# Dongle.net
KiCad netlist of a schematic drawn in Altium Designer
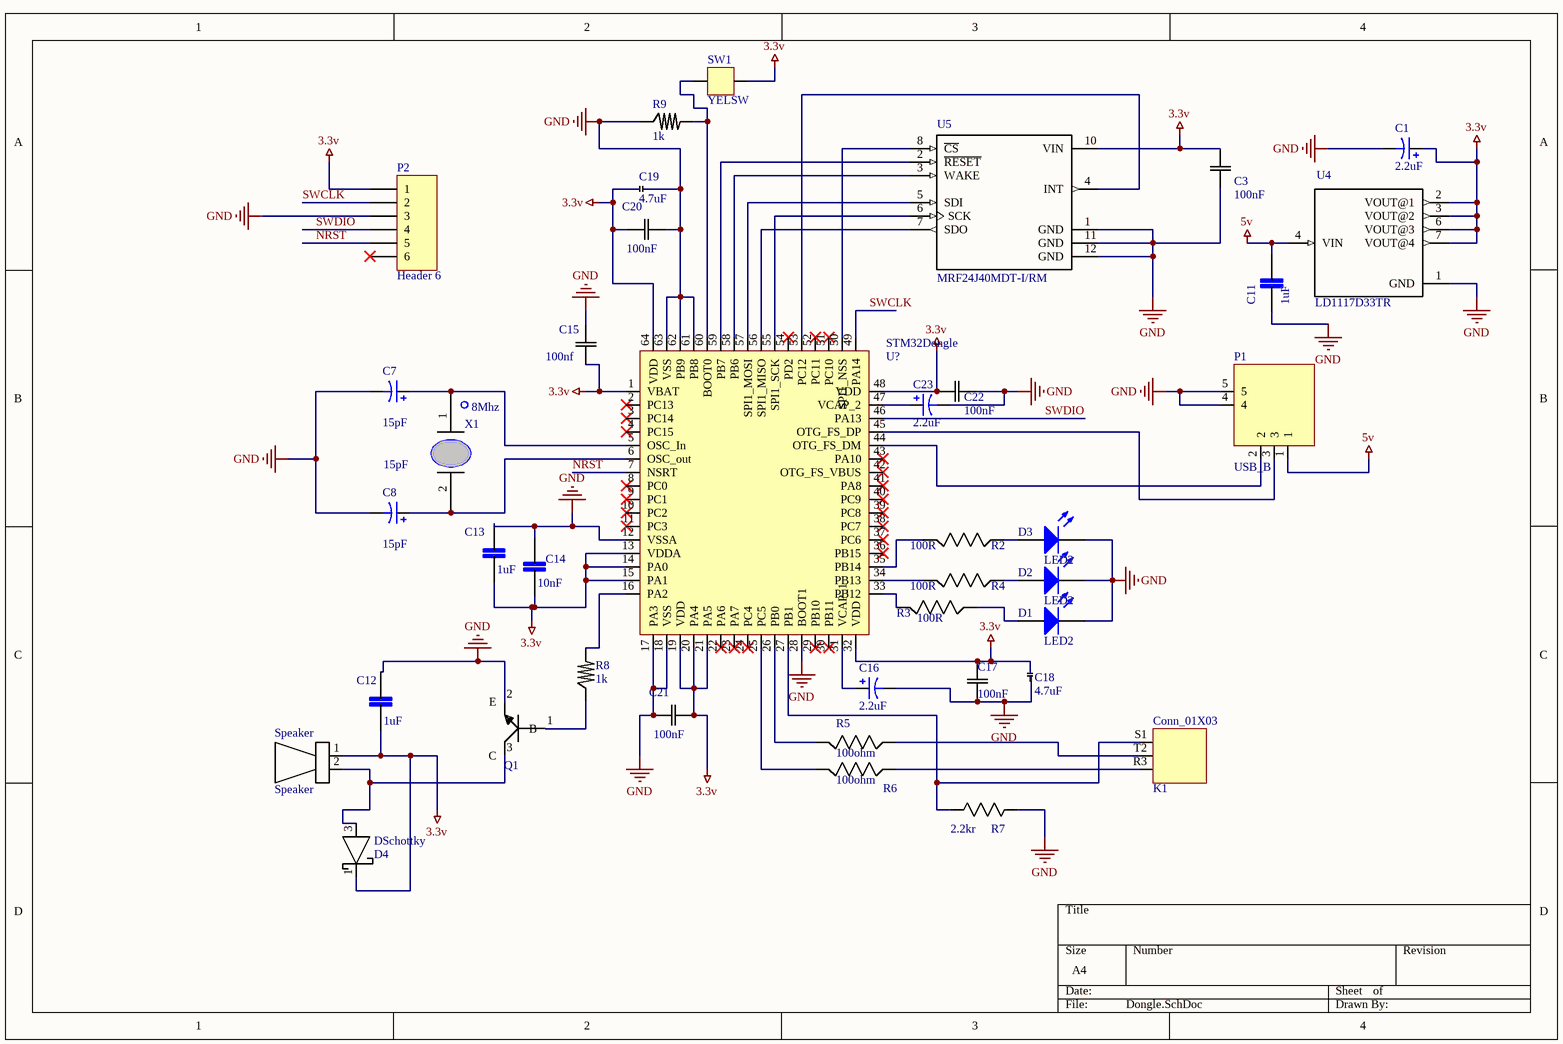
[diagram p0: Dongle.SchDoc]

(export (version "E")
  (design (tool "Eeschema 10.0.6"))
  (components
    (comp (ref "8Mhz")
      (value "X1")
      (footprint "XTAL_ABLS2-24.000MHZ-D4YF-T")
      (libsource (lib "8MhzCrystal") (part "8Mhz"))
    )
    (comp (ref "C1")
      (value "2.2uF")
      (footprint "C0805")
      (description "Polarized Capacitor (Surface Mount)")
      (fields (field (name "Comment") "Cap Pol3") (field (name "PUBLISHER") "Altium Limited"))
      (libsource (lib "Miscellaneous Devices") (part "Cap Pol3"))
    )
    (comp (ref "C3")
      (value "100nF")
      (footprint "CAPC2013X110N")
      (description "Capacitor; Ceramic; Cap; .100UF ; Tol+-10%; SMD; Vol-Rtg 50V; X7R, Tape/Reel")
      (fields (field (name "MP") "C0805C104K5RACTU") (field (name "MF") "Kemet"))
      (libsource (lib "100nF-C0805C104K5RACTU") (part "C0805C104K5RACTU"))
    )
    (comp (ref "C7")
      (value "15pF")
      (footprint "C0805")
      (description "Polarized Capacitor (Surface Mount)")
      (fields (field (name "ALTIUM_VALUE") "15pF") (field (name "PUBLISHER") "Altium Limited"))
      (libsource (lib "Miscellaneous Devices") (part "Cap Pol3"))
    )
    (comp (ref "C8")
      (value "15pF")
      (footprint "C0805")
      (description "Polarized Capacitor (Surface Mount)")
      (fields (field (name "Comment") "Cap Pol3") (field (name "PUBLISHER") "Altium Limited"))
      (libsource (lib "Miscellaneous Devices") (part "Cap Pol3"))
    )
    (comp (ref "C11")
      (value "1uF")
      (footprint "INDC2012X87N")
      (description "CAP CER 1UF 25V X5R 0805")
      (fields (field (name "MF") "TDK") (field (name "MP") "C2012X5R1E105M085AC"))
      (libsource (lib "1uF") (part "C2012X5R1E105M085AC"))
    )
    (comp (ref "C12")
      (value "1uF")
      (footprint "INDC2012X87N")
      (description "CAP CER 1UF 25V X5R 0805")
      (fields (field (name "MF") "TDK") (field (name "MP") "C2012X5R1E105M085AC"))
      (libsource (lib "1uF") (part "C2012X5R1E105M085AC"))
    )
    (comp (ref "C13")
      (value "1uF")
      (footprint "INDC2012X87N")
      (description "CAP CER 1UF 25V X5R 0805")
      (fields (field (name "MF") "TDK") (field (name "MP") "C2012X5R1E105M085AC"))
      (libsource (lib "") (part "C2012X5R1E105M085AC_1"))
    )
    (comp (ref "C14")
      (value "10nF")
      (footprint "CAPC2012X135N")
      (description "CAP CER 10000PF 50V X7R 0805")
      (fields (field (name "MF") "Murata") (field (name "DIGI-KEY_PART_NUMBER") "490-1664-1-ND"))
      (libsource (lib "10nF") (part "GRM216R71H103KA01D"))
    )
    (comp (ref "C15")
      (value "100nf")
      (footprint "CAPC2013X110N")
      (description "Capacitor; Ceramic; Cap; .100UF ; Tol+-10%; SMD; Vol-Rtg 50V; X7R, Tape/Reel")
      (fields (field (name "MP") "C0805C104K5RACTU") (field (name "MF") "Kemet"))
      (libsource (lib "") (part "C0805C104K5RACTU_1"))
    )
    (comp (ref "C16")
      (value "2.2uF")
      (footprint "C0805")
      (description "Polarized Capacitor (Surface Mount)")
      (fields (field (name "Comment") "Cap Pol3") (field (name "PUBLISHER") "Altium Limited"))
      (libsource (lib "Miscellaneous Devices") (part "Cap Pol3"))
    )
    (comp (ref "C17")
      (value "100nF")
      (footprint "CAPC2013X110N")
      (description "Capacitor; Ceramic; Cap; .100UF ; Tol+-10%; SMD; Vol-Rtg 50V; X7R, Tape/Reel")
      (fields (field (name "MP") "C0805C104K5RACTU") (field (name "MF") "Kemet"))
      (libsource (lib "") (part "C0805C104K5RACTU_2"))
    )
    (comp (ref "C18") (value "4.7uF") (footprint "0805") (libsource (lib "4.7uF") (part "4.7uF")))
    (comp (ref "C19") (value "4.7uF") (footprint "0805") (libsource (lib "4.7uF") (part "4.7uF")))
    (comp (ref "C20")
      (value "100nF")
      (footprint "CAPC2013X110N")
      (description "Capacitor; Ceramic; Cap; .100UF ; Tol+-10%; SMD; Vol-Rtg 50V; X7R, Tape/Reel")
      (fields (field (name "MP") "C0805C104K5RACTU") (field (name "MF") "Kemet"))
      (libsource (lib "100nF-C0805C104K5RACTU") (part "C0805C104K5RACTU"))
    )
    (comp (ref "C21")
      (value "100nF")
      (footprint "CAPC2013X110N")
      (description "Capacitor; Ceramic; Cap; .100UF ; Tol+-10%; SMD; Vol-Rtg 50V; X7R, Tape/Reel")
      (fields (field (name "MP") "C0805C104K5RACTU") (field (name "MF") "Kemet"))
      (libsource (lib "100nF-C0805C104K5RACTU") (part "C0805C104K5RACTU"))
    )
    (comp (ref "C22")
      (value "100nF")
      (footprint "CAPC2013X110N")
      (description "Capacitor; Ceramic; Cap; .100UF ; Tol+-10%; SMD; Vol-Rtg 50V; X7R, Tape/Reel")
      (fields (field (name "MP") "C0805C104K5RACTU") (field (name "MF") "Kemet"))
      (libsource (lib "100nF-C0805C104K5RACTU") (part "C0805C104K5RACTU"))
    )
    (comp (ref "C23")
      (value "2.2uF")
      (footprint "C0805")
      (description "Polarized Capacitor (Surface Mount)")
      (fields (field (name "Comment") "Cap Pol3") (field (name "PUBLISHER") "Altium Limited"))
      (libsource (lib "Miscellaneous Devices") (part "Cap Pol3"))
    )
    (comp (ref "Conn_01X03")
      (value "K1")
      (footprint "PCBComponent_1")
      (libsource (lib "MiCInput") (part "Conn_01X03"))
    )
    (comp (ref "D1")
      (value "LED2")
      (footprint "3.2X1.6X1.1")
      (description "Typical RED, GREEN, YELLOW, AMBER GaAs LED")
      (fields (field (name "PUBLISHER") "Altium Limited"))
      (libsource (lib "Miscellaneous Devices") (part "LED2"))
    )
    (comp (ref "D2")
      (value "LED2")
      (footprint "3.2X1.6X1.1")
      (description "Typical RED, GREEN, YELLOW, AMBER GaAs LED")
      (fields (field (name "PUBLISHER") "Altium Limited"))
      (libsource (lib "Miscellaneous Devices") (part "LED2"))
    )
    (comp (ref "D3")
      (value "LED2")
      (footprint "3.2X1.6X1.1")
      (description "Typical RED, GREEN, YELLOW, AMBER GaAs LED")
      (fields (field (name "PUBLISHER") "Altium Limited"))
      (libsource (lib "Miscellaneous Devices") (part "LED2"))
    )
    (comp (ref "DSchottky")
      (value "D4")
      (footprint "SOT65P210X110-3N")
      (libsource (lib "DSchotkky") (part "DSchottky"))
    )
    (comp (ref "P1")
      (value "USB_B")
      (footprint "PCBComponent_1")
      (libsource (lib "USB_B_Female") (part "Component_1"))
    )
    (comp (ref "P2")
      (value "Header 6")
      (footprint "HDR1X6")
      (description "Header, 6-Pin")
      (fields (field (name "PUBLISHER") "Altium Limited"))
      (libsource (lib "Miscellaneous Connectors") (part "Header 6"))
    )
    (comp (ref "Q1")
      (value "BC846A-7-F")
      (footprint "SOT23-3")
      (description "TRANS NPN 65V 0.1A SOT23-3")
      (fields (field (name "MF") "Diodes Inc.") (field (name "DIGI-KEY_PART_NUMBER") "BC846A-7FDICT-ND"))
      (libsource (lib "NPN") (part "BC846A-7-F"))
    )
    (comp (ref "R2")
      (value "100R")
      (footprint "RESC2012X60")
      (description "RES SMD 100 OHM 1% 1/8W 0805")
      (fields (field (name "MP") "RC0805FR-07100RL") (field (name "MF") "Yageo"))
      (libsource (lib "RC0805FR-07100RL") (part "RC0805FR-07100RL"))
    )
    (comp (ref "R3")
      (value "100R")
      (footprint "RESC2012X60")
      (description "RES SMD 100 OHM 1% 1/8W 0805")
      (fields (field (name "MP") "RC0805FR-07100RL") (field (name "MF") "Yageo"))
      (libsource (lib "RC0805FR-07100RL") (part "RC0805FR-07100RL"))
    )
    (comp (ref "R4")
      (value "100R")
      (footprint "RESC2012X60")
      (description "RES SMD 100 OHM 1% 1/8W 0805")
      (fields (field (name "MP") "RC0805FR-07100RL") (field (name "MF") "Yageo"))
      (libsource (lib "RC0805FR-07100RL") (part "RC0805FR-07100RL"))
    )
    (comp (ref "R5")
      (value "100ohm")
      (footprint "RESC2012X60")
      (description "RES SMD 100 OHM 1% 1/8W 0805")
      (fields (field (name "MP") "RC0805FR-07100RL") (field (name "MF") "Yageo"))
      (libsource (lib "RC0805FR-07100RL") (part "RC0805FR-07100RL"))
    )
    (comp (ref "R6")
      (value "100ohm")
      (footprint "RESC2012X60")
      (description "RES SMD 100 OHM 1% 1/8W 0805")
      (fields (field (name "MP") "RC0805FR-07100RL") (field (name "MF") "Yageo"))
      (libsource (lib "RC0805FR-07100RL") (part "RC0805FR-07100RL"))
    )
    (comp (ref "R7")
      (value "2.2kr")
      (footprint "RESC2013X65N")
      (description "RES SMD 2.2K OHM 1% 1/8W 0805")
      (fields (field (name "MP") "RC0805FR-072K2L") (field (name "MF") "Yageo"))
      (libsource (lib "RC0805FR-072K2L") (part "RC0805FR-072K2L"))
    )
    (comp (ref "R8")
      (value "1k")
      (footprint "CAPC2012X140N")
      (description "1276-5272-1-ND")
      (libsource (lib "1k") (part "1kohm"))
    )
    (comp (ref "R9")
      (value "1k")
      (footprint "CAPC2012X140N")
      (description "1276-5272-1-ND")
      (libsource (lib "1k") (part "1kohm"))
    )
    (comp (ref "Speaker")
      (value "Speaker")
      (footprint "Speaker")
      (libsource (lib "Speaker") (part "Component_1"))
    )
    (comp (ref "STM32Dongle")
      (value "U?")
      (footprint "QFP50P1200X1200X160-64N")
      (description "497-11907-ND")
      (libsource (lib "STM32F415RGT6") (part "STM32Dongle"))
    )
    (comp (ref "SW1")
      (value "YELSW")
      (footprint "PCBComponent_1")
      (libsource (lib "EG2555-ND") (part "YELSW"))
    )
    (comp (ref "U4")
      (value "LD1117D33TR")
      (footprint "SOIC127P600X175-8N")
      (description "IC REG LINEAR 3.3V 800MA 8SO")
      (fields (field (name "MF") "STMicroelectronics"))
      (libsource (lib "LD1117D33TR") (part "LD1117D33TR"))
    )
    (comp (ref "U5")
      (value "MRF24J40MDT-I/RM")
      (footprint "XCVR_MRF24J40MDT-I/RM")
      (description "2.4 GHz IEEE 802.15.4 Certified Transceiver Module (+20 dBm), 12 MODULE Varies T/R")
      (fields (field (name "MF") "Microchip"))
      (libsource (lib "MRF24J40MDT-I_RM") (part "MRF24J40MDT-I/RM"))
    )
  )
  (nets
    (net (code "1") (name "/NRST") (class "Default")
      (node (ref "P2") (pin "5") (pinfunction "5_5") (pintype "passive"))
      (node (ref "STM32Dongle") (pin "7") (pinfunction "NSRT_7") (pintype "passive"))
    )
    (net (code "2") (name "/SWCLK") (class "Default")
      (node (ref "P2") (pin "2") (pinfunction "2_2") (pintype "passive"))
      (node (ref "STM32Dongle") (pin "49") (pinfunction "PA14_49") (pintype "passive"))
    )
    (net (code "3") (name "/SWDIO") (class "Default")
      (node (ref "P2") (pin "4") (pinfunction "4_4") (pintype "passive"))
      (node (ref "STM32Dongle") (pin "46") (pinfunction "PA13_46") (pintype "passive"))
    )
    (net (code "4") (name "3.3v") (class "Default")
      (node (ref "C1") (pin "1") (pinfunction "1_1") (pintype "passive"))
      (node (ref "C12") (pin "1") (pinfunction "1_1") (pintype "passive"))
      (node (ref "C13") (pin "1") (pinfunction "1_1") (pintype "passive"))
      (node (ref "C14") (pin "1") (pinfunction "1_1") (pintype "passive"))
      (node (ref "C15") (pin "1") (pinfunction "C1_1") (pintype "passive"))
      (node (ref "C17") (pin "1") (pinfunction "C1_1") (pintype "passive"))
      (node (ref "C18") (pin "P1") (pinfunction "P1_P1") (pintype "passive"))
      (node (ref "C19") (pin "P1") (pinfunction "P1_P1") (pintype "passive"))
      (node (ref "C20") (pin "1") (pinfunction "C1_1") (pintype "passive"))
      (node (ref "C21") (pin "2") (pinfunction "C2_2") (pintype "passive"))
      (node (ref "C22") (pin "1") (pinfunction "C1_1") (pintype "passive"))
      (node (ref "C3") (pin "1") (pinfunction "C1_1") (pintype "passive"))
      (node (ref "DSchottky") (pin "1") (pinfunction "1_1") (pintype "passive"))
      (node (ref "P2") (pin "1") (pinfunction "1_1") (pintype "passive"))
      (node (ref "STM32Dongle") (pin "1") (pinfunction "VBAT_1") (pintype "passive"))
      (node (ref "STM32Dongle") (pin "13") (pinfunction "VDDA_13") (pintype "passive"))
      (node (ref "STM32Dongle") (pin "14") (pinfunction "PA0_14") (pintype "passive"))
      (node (ref "STM32Dongle") (pin "15") (pinfunction "PA1_15") (pintype "passive"))
      (node (ref "STM32Dongle") (pin "19") (pinfunction "VDD_19") (pintype "passive"))
      (node (ref "STM32Dongle") (pin "20") (pinfunction "PA4_20") (pintype "passive"))
      (node (ref "STM32Dongle") (pin "21") (pinfunction "PA5_21") (pintype "passive"))
      (node (ref "STM32Dongle") (pin "32") (pinfunction "VDD_32") (pintype "passive"))
      (node (ref "STM32Dongle") (pin "48") (pinfunction "VDD_48") (pintype "passive"))
      (node (ref "STM32Dongle") (pin "64") (pinfunction "VDD_64") (pintype "passive"))
      (node (ref "SW1") (pin "3") (pinfunction "3_3") (pintype "passive"))
      (node (ref "Speaker") (pin "1") (pinfunction "1_1") (pintype "passive"))
      (node (ref "U4") (pin "2") (pinfunction "VOUT@1_2") (pintype "output"))
      (node (ref "U4") (pin "3") (pinfunction "VOUT@2_3") (pintype "output"))
      (node (ref "U4") (pin "6") (pinfunction "VOUT@3_6") (pintype "output"))
      (node (ref "U4") (pin "7") (pinfunction "VOUT@4_7") (pintype "output"))
      (node (ref "U5") (pin "10") (pinfunction "VIN_10") (pintype "power_in"))
    )
    (net (code "5") (name "5v") (class "Default")
      (node (ref "C11") (pin "2") (pinfunction "2_2") (pintype "passive"))
      (node (ref "P1") (pin "1") (pinfunction "1_1") (pintype "passive"))
      (node (ref "U4") (pin "4") (pinfunction "VIN_4") (pintype "input"))
    )
    (net (code "6") (name "GND") (class "Default")
      (node (ref "C1") (pin "2") (pinfunction "2_2") (pintype "passive"))
      (node (ref "C11") (pin "1") (pinfunction "1_1") (pintype "passive"))
      (node (ref "C12") (pin "2") (pinfunction "2_2") (pintype "passive"))
      (node (ref "C13") (pin "2") (pinfunction "2_2") (pintype "passive"))
      (node (ref "C14") (pin "2") (pinfunction "2_2") (pintype "passive"))
      (node (ref "C15") (pin "2") (pinfunction "C2_2") (pintype "passive"))
      (node (ref "C16") (pin "2") (pinfunction "2_2") (pintype "passive"))
      (node (ref "C17") (pin "2") (pinfunction "C2_2") (pintype "passive"))
      (node (ref "C18") (pin "P2") (pinfunction "P2_P2") (pintype "passive"))
      (node (ref "C19") (pin "P2") (pinfunction "P2_P2") (pintype "passive"))
      (node (ref "C20") (pin "2") (pinfunction "C2_2") (pintype "passive"))
      (node (ref "C21") (pin "1") (pinfunction "C1_1") (pintype "passive"))
      (node (ref "C22") (pin "2") (pinfunction "C2_2") (pintype "passive"))
      (node (ref "C23") (pin "2") (pinfunction "2_2") (pintype "passive"))
      (node (ref "C3") (pin "2") (pinfunction "C2_2") (pintype "passive"))
      (node (ref "C7") (pin "2") (pinfunction "2_2") (pintype "passive"))
      (node (ref "C8") (pin "2") (pinfunction "2_2") (pintype "passive"))
      (node (ref "D1") (pin "2") (pinfunction "K_2") (pintype "passive"))
      (node (ref "D2") (pin "2") (pinfunction "K_2") (pintype "passive"))
      (node (ref "D3") (pin "2") (pinfunction "K_2") (pintype "passive"))
      (node (ref "P1") (pin "4") (pinfunction "4_4") (pintype "passive"))
      (node (ref "P1") (pin "5") (pinfunction "5_5") (pintype "passive"))
      (node (ref "P2") (pin "3") (pinfunction "3_3") (pintype "passive"))
      (node (ref "Q1") (pin "2") (pinfunction "E_2") (pintype "bidirectional"))
      (node (ref "R7") (pin "1") (pinfunction "R1_1") (pintype "passive"))
      (node (ref "R9") (pin "1") (pinfunction "1_1") (pintype "passive"))
      (node (ref "STM32Dongle") (pin "12") (pinfunction "VSSA_12") (pintype "passive"))
      (node (ref "STM32Dongle") (pin "17") (pinfunction "PA3_17") (pintype "passive"))
      (node (ref "STM32Dongle") (pin "18") (pinfunction "VSS_18") (pintype "passive"))
      (node (ref "STM32Dongle") (pin "28") (pinfunction "BOOT1_28") (pintype "passive"))
      (node (ref "STM32Dongle") (pin "61") (pinfunction "PB8_61") (pintype "passive"))
      (node (ref "STM32Dongle") (pin "62") (pinfunction "PB9_62") (pintype "passive"))
      (node (ref "STM32Dongle") (pin "63") (pinfunction "VSS_63") (pintype "passive"))
      (node (ref "U4") (pin "1") (pinfunction "GND_1") (pintype "power_in"))
      (node (ref "U5") (pin "1") (pinfunction "GND_1") (pintype "power_in"))
      (node (ref "U5") (pin "11") (pinfunction "GND_11") (pintype "power_in"))
      (node (ref "U5") (pin "12") (pinfunction "GND_12") (pintype "power_in"))
    )
    (net (code "7") (name "Net-(Conn_01X03-PadR3)") (class "Default")
      (node (ref "Conn_01X03") (pin "R3") (pinfunction "R3_R3") (pintype "passive"))
      (node (ref "R6") (pin "2") (pinfunction "2_2") (pintype "passive"))
    )
    (net (code "8") (name "Net-(Conn_01X03-PadT2)") (class "Default")
      (node (ref "Conn_01X03") (pin "T2") (pinfunction "T2_T2") (pintype "passive"))
      (node (ref "R5") (pin "2") (pinfunction "2_2") (pintype "passive"))
    )
    (net (code "9") (name "Net-(D1-A)") (class "Default")
      (node (ref "D1") (pin "1") (pinfunction "A_1") (pintype "passive"))
      (node (ref "R3") (pin "2") (pinfunction "2_2") (pintype "passive"))
    )
    (net (code "10") (name "Net-(D2-A)") (class "Default")
      (node (ref "D2") (pin "1") (pinfunction "A_1") (pintype "passive"))
      (node (ref "R4") (pin "2") (pinfunction "2_2") (pintype "passive"))
    )
    (net (code "11") (name "Net-(D3-A)") (class "Default")
      (node (ref "D3") (pin "1") (pinfunction "A_1") (pintype "passive"))
      (node (ref "R2") (pin "2") (pinfunction "2_2") (pintype "passive"))
    )
    (net (code "12") (name "Net-(Q1-B)") (class "Default")
      (node (ref "Q1") (pin "1") (pinfunction "B_1") (pintype "bidirectional"))
      (node (ref "R8") (pin "1") (pinfunction "1_1") (pintype "passive"))
    )
    (net (code "13") (name "Net-(Q1-C)") (class "Default")
      (node (ref "DSchottky") (pin "3") (pinfunction "3_3") (pintype "passive"))
      (node (ref "Q1") (pin "3") (pinfunction "C_3") (pintype "bidirectional"))
      (node (ref "Speaker") (pin "2") (pinfunction "2_2") (pintype "passive"))
    )
    (net (code "14") (name "Net-(R7-R2)") (class "Default")
      (node (ref "Conn_01X03") (pin "S1") (pinfunction "S1_S1") (pintype "passive"))
      (node (ref "R7") (pin "2") (pinfunction "R2_2") (pintype "passive"))
      (node (ref "STM32Dongle") (pin "27") (pinfunction "PB1_27") (pintype "passive"))
    )
    (net (code "15") (name "Net-(STM32Dongle-BOOT0)") (class "Default")
      (node (ref "R9") (pin "2") (pinfunction "2_2") (pintype "passive"))
      (node (ref "STM32Dongle") (pin "60") (pinfunction "BOOT0_60") (pintype "passive"))
      (node (ref "SW1") (pin "1") (pinfunction "1_1") (pintype "passive"))
    )
    (net (code "16") (name "Net-(STM32Dongle-OSC_In)") (class "Default")
      (node (ref "8Mhz") (pin "1") (pinfunction "1_1") (pintype "passive"))
      (node (ref "C7") (pin "1") (pinfunction "1_1") (pintype "passive"))
      (node (ref "STM32Dongle") (pin "5") (pinfunction "OSC_In_5") (pintype "passive"))
    )
    (net (code "17") (name "Net-(STM32Dongle-OSC_out)") (class "Default")
      (node (ref "8Mhz") (pin "2") (pinfunction "2_2") (pintype "passive"))
      (node (ref "C8") (pin "1") (pinfunction "1_1") (pintype "passive"))
      (node (ref "STM32Dongle") (pin "6") (pinfunction "OSC_out_6") (pintype "passive"))
    )
    (net (code "18") (name "Net-(STM32Dongle-OTG_FS_DM)") (class "Default")
      (node (ref "P1") (pin "2") (pinfunction "2_2") (pintype "passive"))
      (node (ref "STM32Dongle") (pin "44") (pinfunction "OTG_FS_DM_44") (pintype "passive"))
    )
    (net (code "19") (name "Net-(STM32Dongle-OTG_FS_DP)") (class "Default")
      (node (ref "P1") (pin "3") (pinfunction "3_3") (pintype "passive"))
      (node (ref "STM32Dongle") (pin "45") (pinfunction "OTG_FS_DP_45") (pintype "passive"))
    )
    (net (code "20") (name "Net-(STM32Dongle-PA2)") (class "Default")
      (node (ref "R8") (pin "2") (pinfunction "2_2") (pintype "passive"))
      (node (ref "STM32Dongle") (pin "16") (pinfunction "PA2_16") (pintype "passive"))
    )
    (net (code "21") (name "Net-(STM32Dongle-PB0)") (class "Default")
      (node (ref "R5") (pin "1") (pinfunction "1_1") (pintype "passive"))
      (node (ref "STM32Dongle") (pin "26") (pinfunction "PB0_26") (pintype "passive"))
    )
    (net (code "22") (name "Net-(STM32Dongle-PB6)") (class "Default")
      (node (ref "STM32Dongle") (pin "58") (pinfunction "PB6_58") (pintype "passive"))
      (node (ref "U5") (pin "3") (pinfunction "WAKE_3") (pintype "input"))
    )
    (net (code "23") (name "Net-(STM32Dongle-PB7)") (class "Default")
      (node (ref "STM32Dongle") (pin "59") (pinfunction "PB7_59") (pintype "passive"))
      (node (ref "U5") (pin "2") (pinfunction "~{RESET}_2") (pintype "input"))
    )
    (net (code "24") (name "Net-(STM32Dongle-PB12)") (class "Default")
      (node (ref "R3") (pin "1") (pinfunction "1_1") (pintype "passive"))
      (node (ref "STM32Dongle") (pin "33") (pinfunction "PB12_33") (pintype "passive"))
    )
    (net (code "25") (name "Net-(STM32Dongle-PB13)") (class "Default")
      (node (ref "R4") (pin "1") (pinfunction "1_1") (pintype "passive"))
      (node (ref "STM32Dongle") (pin "34") (pinfunction "PB13_34") (pintype "passive"))
    )
    (net (code "26") (name "Net-(STM32Dongle-PB14)") (class "Default")
      (node (ref "R2") (pin "1") (pinfunction "1_1") (pintype "passive"))
      (node (ref "STM32Dongle") (pin "35") (pinfunction "PB14_35") (pintype "passive"))
    )
    (net (code "27") (name "Net-(STM32Dongle-PC5)") (class "Default")
      (node (ref "R6") (pin "1") (pinfunction "1_1") (pintype "passive"))
      (node (ref "STM32Dongle") (pin "25") (pinfunction "PC5_25") (pintype "passive"))
    )
    (net (code "28") (name "Net-(STM32Dongle-PC12)") (class "Default")
      (node (ref "STM32Dongle") (pin "53") (pinfunction "PC12_53") (pintype "passive"))
      (node (ref "U5") (pin "4") (pinfunction "INT_4") (pintype "output"))
    )
    (net (code "29") (name "Net-(STM32Dongle-SPI1_MISO)") (class "Default")
      (node (ref "STM32Dongle") (pin "56") (pinfunction "SPI1_MISO_56") (pintype "passive"))
      (node (ref "U5") (pin "7") (pinfunction "SDO_7") (pintype "output"))
    )
    (net (code "30") (name "Net-(STM32Dongle-SPI1_MOSI)") (class "Default")
      (node (ref "STM32Dongle") (pin "57") (pinfunction "SPI1_MOSI_57") (pintype "passive"))
      (node (ref "U5") (pin "5") (pinfunction "SDI_5") (pintype "input"))
    )
    (net (code "31") (name "Net-(STM32Dongle-SPI1_NSS)") (class "Default")
      (node (ref "STM32Dongle") (pin "50") (pinfunction "SPI1_NSS_50") (pintype "passive"))
      (node (ref "U5") (pin "8") (pinfunction "~{CS}_8") (pintype "input"))
    )
    (net (code "32") (name "Net-(STM32Dongle-SPI1_SCK)") (class "Default")
      (node (ref "STM32Dongle") (pin "55") (pinfunction "SPI1_SCK_55") (pintype "passive"))
      (node (ref "U5") (pin "6") (pinfunction "SCK_6") (pintype "input"))
    )
    (net (code "33") (name "Net-(STM32Dongle-VCAP_1)") (class "Default")
      (node (ref "C16") (pin "1") (pinfunction "1_1") (pintype "passive"))
      (node (ref "STM32Dongle") (pin "31") (pinfunction "VCAP_1_31") (pintype "passive"))
    )
    (net (code "34") (name "Net-(STM32Dongle-VCAP_2)") (class "Default")
      (node (ref "C23") (pin "1") (pinfunction "1_1") (pintype "passive"))
      (node (ref "STM32Dongle") (pin "47") (pinfunction "VCAP_2_47") (pintype "passive"))
    )
    (net (code "35") (name "unconnected-(P2-Pad6)") (class "Default")
      (node (ref "P2") (pin "6") (pinfunction "6_6") (pintype "passive+no_connect"))
    )
    (net (code "36") (name "unconnected-(STM32Dongle-OTG_FS_VBUS-Pad42)") (class "Default")
      (node (ref "STM32Dongle") (pin "42") (pinfunction "OTG_FS_VBUS_42") (pintype "passive+no_connect"))
    )
    (net (code "37") (name "unconnected-(STM32Dongle-PA6-Pad22)") (class "Default")
      (node (ref "STM32Dongle") (pin "22") (pinfunction "PA6_22") (pintype "passive+no_connect"))
    )
    (net (code "38") (name "unconnected-(STM32Dongle-PA7-Pad23)") (class "Default")
      (node (ref "STM32Dongle") (pin "23") (pinfunction "PA7_23") (pintype "passive+no_connect"))
    )
    (net (code "39") (name "unconnected-(STM32Dongle-PA8-Pad41)") (class "Default")
      (node (ref "STM32Dongle") (pin "41") (pinfunction "PA8_41") (pintype "passive+no_connect"))
    )
    (net (code "40") (name "unconnected-(STM32Dongle-PA10-Pad43)") (class "Default")
      (node (ref "STM32Dongle") (pin "43") (pinfunction "PA10_43") (pintype "passive+no_connect"))
    )
    (net (code "41") (name "unconnected-(STM32Dongle-PB10-Pad29)") (class "Default")
      (node (ref "STM32Dongle") (pin "29") (pinfunction "PB10_29") (pintype "passive+no_connect"))
    )
    (net (code "42") (name "unconnected-(STM32Dongle-PB11-Pad30)") (class "Default")
      (node (ref "STM32Dongle") (pin "30") (pinfunction "PB11_30") (pintype "passive+no_connect"))
    )
    (net (code "43") (name "unconnected-(STM32Dongle-PB15-Pad36)") (class "Default")
      (node (ref "STM32Dongle") (pin "36") (pinfunction "PB15_36") (pintype "passive+no_connect"))
    )
    (net (code "44") (name "unconnected-(STM32Dongle-PC0-Pad8)") (class "Default")
      (node (ref "STM32Dongle") (pin "8") (pinfunction "PC0_8") (pintype "passive+no_connect"))
    )
    (net (code "45") (name "unconnected-(STM32Dongle-PC1-Pad9)") (class "Default")
      (node (ref "STM32Dongle") (pin "9") (pinfunction "PC1_9") (pintype "passive+no_connect"))
    )
    (net (code "46") (name "unconnected-(STM32Dongle-PC2-Pad10)") (class "Default")
      (node (ref "STM32Dongle") (pin "10") (pinfunction "PC2_10") (pintype "passive+no_connect"))
    )
    (net (code "47") (name "unconnected-(STM32Dongle-PC3-Pad11)") (class "Default")
      (node (ref "STM32Dongle") (pin "11") (pinfunction "PC3_11") (pintype "passive+no_connect"))
    )
    (net (code "48") (name "unconnected-(STM32Dongle-PC4-Pad24)") (class "Default")
      (node (ref "STM32Dongle") (pin "24") (pinfunction "PC4_24") (pintype "passive+no_connect"))
    )
    (net (code "49") (name "unconnected-(STM32Dongle-PC6-Pad37)") (class "Default")
      (node (ref "STM32Dongle") (pin "37") (pinfunction "PC6_37") (pintype "passive+no_connect"))
    )
    (net (code "50") (name "unconnected-(STM32Dongle-PC7-Pad38)") (class "Default")
      (node (ref "STM32Dongle") (pin "38") (pinfunction "PC7_38") (pintype "passive+no_connect"))
    )
    (net (code "51") (name "unconnected-(STM32Dongle-PC8-Pad39)") (class "Default")
      (node (ref "STM32Dongle") (pin "39") (pinfunction "PC8_39") (pintype "passive+no_connect"))
    )
    (net (code "52") (name "unconnected-(STM32Dongle-PC9-Pad40)") (class "Default")
      (node (ref "STM32Dongle") (pin "40") (pinfunction "PC9_40") (pintype "passive+no_connect"))
    )
    (net (code "53") (name "unconnected-(STM32Dongle-PC10-Pad51)") (class "Default")
      (node (ref "STM32Dongle") (pin "51") (pinfunction "PC10_51") (pintype "passive+no_connect"))
    )
    (net (code "54") (name "unconnected-(STM32Dongle-PC11-Pad52)") (class "Default")
      (node (ref "STM32Dongle") (pin "52") (pinfunction "PC11_52") (pintype "passive+no_connect"))
    )
    (net (code "55") (name "unconnected-(STM32Dongle-PC13-Pad2)") (class "Default")
      (node (ref "STM32Dongle") (pin "2") (pinfunction "PC13_2") (pintype "passive+no_connect"))
    )
    (net (code "56") (name "unconnected-(STM32Dongle-PC14-Pad3)") (class "Default")
      (node (ref "STM32Dongle") (pin "3") (pinfunction "PC14_3") (pintype "passive+no_connect"))
    )
    (net (code "57") (name "unconnected-(STM32Dongle-PC15-Pad4)") (class "Default")
      (node (ref "STM32Dongle") (pin "4") (pinfunction "PC15_4") (pintype "passive+no_connect"))
    )
    (net (code "58") (name "unconnected-(STM32Dongle-PD2-Pad54)") (class "Default")
      (node (ref "STM32Dongle") (pin "54") (pinfunction "PD2_54") (pintype "passive+no_connect"))
    )
  )
)
